# Sheet1.net
KiCad netlist of a schematic drawn in Altium Designer
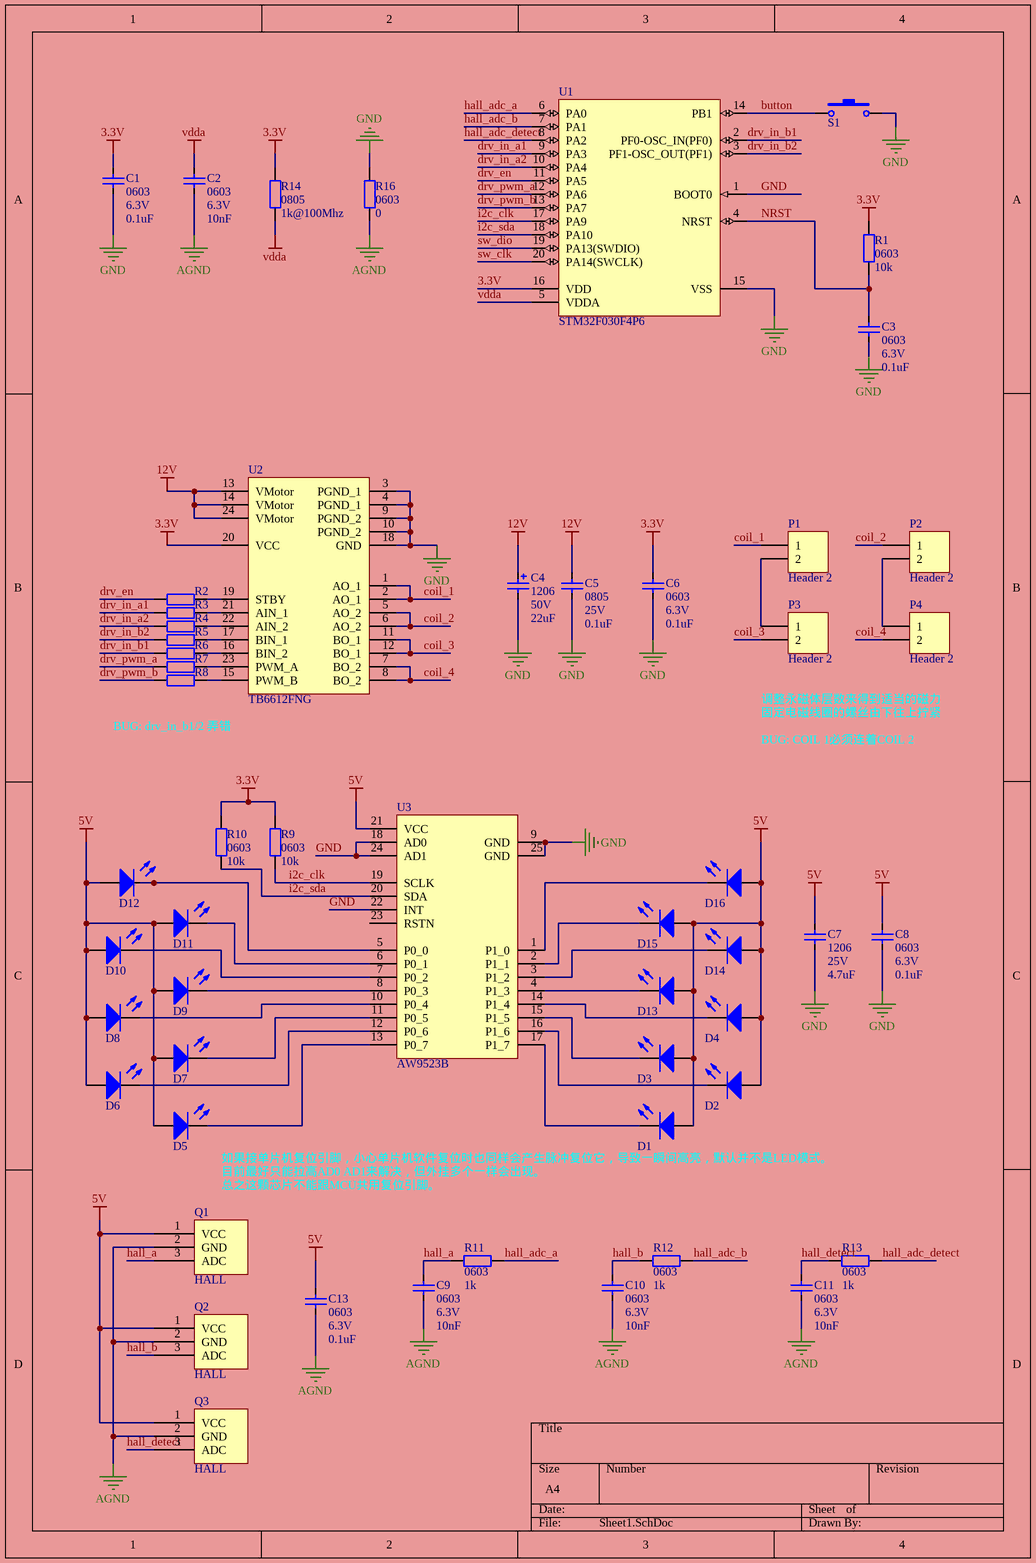
[diagram p0: Sheet1.SchDoc]

(export (version "E")
  (design (tool "Eeschema 10.0.6"))
  (components
    (comp (ref "C1")
      (value "0.1uF")
      (footprint "0603")
      (description "Capacitor 0603")
      (fields (field (name "VOLTAGE") "6.3V") (field (name "Comment") "CAP_0603"))
      (libsource (lib "Charles_Schlib") (part "CAP_0603"))
    )
    (comp (ref "C2")
      (value "10nF")
      (footprint "0603")
      (description "Capacitor 0603")
      (fields (field (name "VOLTAGE") "6.3V") (field (name "Comment") "CAP_0603"))
      (libsource (lib "Charles_Schlib") (part "CAP_0603"))
    )
    (comp (ref "C3")
      (value "0.1uF")
      (footprint "0603")
      (description "Capacitor 0603")
      (fields (field (name "VOLTAGE") "6.3V") (field (name "Comment") "CAP_0603"))
      (libsource (lib "Charles_Schlib") (part "CAP_0603"))
    )
    (comp (ref "C4")
      (value "22uF")
      (footprint "1206")
      (description "aluminium electrolysis")
      (fields (field (name "VOLTAGE") "50V") (field (name "Comment") "CAP_Aluminium"))
      (libsource (lib "Charles_Schlib") (part "CAP_Aluminium"))
    )
    (comp (ref "C5")
      (value "0.1uF")
      (footprint "0805")
      (description "Capacitor 0805")
      (fields (field (name "VOLTAGE") "25V") (field (name "Comment") "CAP_0805"))
      (libsource (lib "Charles_Schlib") (part "CAP_0805"))
    )
    (comp (ref "C6")
      (value "0.1uF")
      (footprint "0603")
      (description "Capacitor 0603")
      (fields (field (name "VOLTAGE") "6.3V") (field (name "Comment") "CAP_0603"))
      (libsource (lib "Charles_Schlib") (part "CAP_0603"))
    )
    (comp (ref "C7")
      (value "4.7uF")
      (footprint "1206")
      (description "Capacitor 1206")
      (fields (field (name "VOLTAGE") "25V") (field (name "Comment") "CAP_1206"))
      (libsource (lib "Charles_Schlib") (part "CAP_1206"))
    )
    (comp (ref "C8")
      (value "0.1uF")
      (footprint "0603")
      (description "Capacitor 0603")
      (fields (field (name "VOLTAGE") "6.3V") (field (name "Comment") "CAP_0603"))
      (libsource (lib "Charles_Schlib") (part "CAP_0603"))
    )
    (comp (ref "C9")
      (value "10nF")
      (footprint "0603")
      (description "Capacitor 0603")
      (fields (field (name "VOLTAGE") "6.3V") (field (name "Comment") "CAP_0603"))
      (libsource (lib "Charles_Schlib") (part "CAP_0603"))
    )
    (comp (ref "C10")
      (value "10nF")
      (footprint "0603")
      (description "Capacitor 0603")
      (fields (field (name "VOLTAGE") "6.3V") (field (name "Comment") "CAP_0603"))
      (libsource (lib "Charles_Schlib") (part "CAP_0603"))
    )
    (comp (ref "C11")
      (value "10nF")
      (footprint "0603")
      (description "Capacitor 0603")
      (fields (field (name "VOLTAGE") "6.3V") (field (name "Comment") "CAP_0603"))
      (libsource (lib "Charles_Schlib") (part "CAP_0603"))
    )
    (comp (ref "C13")
      (value "0.1uF")
      (footprint "0603")
      (description "Capacitor 0603")
      (fields (field (name "VOLTAGE") "6.3V") (field (name "Comment") "CAP_0603"))
      (libsource (lib "Charles_Schlib") (part "CAP_0603"))
    )
    (comp (ref "D1")
      (value "LED")
      (footprint "LED_DIP")
      (description "LED_DIP")
      (libsource (lib "Charles_Schlib") (part "LED_DIP"))
    )
    (comp (ref "D2")
      (value "LED")
      (footprint "LED_DIP")
      (description "LED_DIP")
      (libsource (lib "Charles_Schlib") (part "LED_DIP"))
    )
    (comp (ref "D3")
      (value "LED")
      (footprint "LED_DIP")
      (description "LED_DIP")
      (libsource (lib "Charles_Schlib") (part "LED_DIP"))
    )
    (comp (ref "D4")
      (value "LED")
      (footprint "LED_DIP")
      (description "LED_DIP")
      (libsource (lib "Charles_Schlib") (part "LED_DIP"))
    )
    (comp (ref "D5")
      (value "LED")
      (footprint "LED_DIP")
      (description "LED_DIP")
      (libsource (lib "Charles_Schlib") (part "LED_DIP"))
    )
    (comp (ref "D6")
      (value "LED")
      (footprint "LED_DIP")
      (description "LED_DIP")
      (libsource (lib "Charles_Schlib") (part "LED_DIP"))
    )
    (comp (ref "D7")
      (value "LED")
      (footprint "LED_DIP")
      (description "LED_DIP")
      (libsource (lib "Charles_Schlib") (part "LED_DIP"))
    )
    (comp (ref "D8")
      (value "LED")
      (footprint "LED_DIP")
      (description "LED_DIP")
      (libsource (lib "Charles_Schlib") (part "LED_DIP"))
    )
    (comp (ref "D9")
      (value "LED")
      (footprint "LED_DIP")
      (description "LED_DIP")
      (libsource (lib "Charles_Schlib") (part "LED_DIP"))
    )
    (comp (ref "D10")
      (value "LED")
      (footprint "LED_DIP")
      (description "LED_DIP")
      (libsource (lib "Charles_Schlib") (part "LED_DIP"))
    )
    (comp (ref "D11")
      (value "LED")
      (footprint "LED_DIP")
      (description "LED_DIP")
      (libsource (lib "Charles_Schlib") (part "LED_DIP"))
    )
    (comp (ref "D12")
      (value "LED")
      (footprint "LED_DIP")
      (description "LED_DIP")
      (libsource (lib "Charles_Schlib") (part "LED_DIP"))
    )
    (comp (ref "D13")
      (value "LED")
      (footprint "LED_DIP")
      (description "LED_DIP")
      (libsource (lib "Charles_Schlib") (part "LED_DIP"))
    )
    (comp (ref "D14")
      (value "LED")
      (footprint "LED_DIP")
      (description "LED_DIP")
      (libsource (lib "Charles_Schlib") (part "LED_DIP"))
    )
    (comp (ref "D15")
      (value "LED")
      (footprint "LED_DIP")
      (description "LED_DIP")
      (libsource (lib "Charles_Schlib") (part "LED_DIP"))
    )
    (comp (ref "D16")
      (value "LED")
      (footprint "LED_DIP")
      (description "LED_DIP")
      (libsource (lib "Charles_Schlib") (part "LED_DIP"))
    )
    (comp (ref "P1")
      (value "Header 2")
      (footprint "HDR1X2")
      (description "Header, 2-Pin")
      (fields (field (name "PUBLISHER") "Altium Limited"))
      (libsource (lib "Miscellaneous Connectors") (part "Header 2"))
    )
    (comp (ref "P2")
      (value "Header 2")
      (footprint "HDR1X2")
      (description "Header, 2-Pin")
      (fields (field (name "PUBLISHER") "Altium Limited"))
      (libsource (lib "Miscellaneous Connectors") (part "Header 2"))
    )
    (comp (ref "P3")
      (value "Header 2")
      (footprint "HDR1X2")
      (description "Header, 2-Pin")
      (fields (field (name "PUBLISHER") "Altium Limited"))
      (libsource (lib "Miscellaneous Connectors") (part "Header 2"))
    )
    (comp (ref "P4")
      (value "Header 2")
      (footprint "HDR1X2")
      (description "Header, 2-Pin")
      (fields (field (name "PUBLISHER") "Altium Limited"))
      (libsource (lib "Miscellaneous Connectors") (part "Header 2"))
    )
    (comp (ref "Q1")
      (value "HALL")
      (footprint "HALL_3503_TO-92")
      (description "HALL SS49E 3503")
      (libsource (lib "Charles_Schlib") (part "SS49E_3503"))
    )
    (comp (ref "Q2")
      (value "HALL")
      (footprint "HALL_3503_TO-92")
      (description "HALL SS49E 3503")
      (libsource (lib "Charles_Schlib") (part "SS49E_3503"))
    )
    (comp (ref "Q3")
      (value "HALL")
      (footprint "HALL_3503_TO-92")
      (description "HALL SS49E 3503")
      (libsource (lib "Charles_Schlib") (part "SS49E_3503"))
    )
    (comp (ref "R1")
      (value "10k")
      (footprint "0603")
      (description "Resister")
      (fields (field (name "Comment") "RES_0603"))
      (libsource (lib "") (part "RES_0603_1"))
    )
    (comp (ref "R2")
      (value "RES_0603")
      (footprint "R0603")
      (description "Resister")
      (libsource (lib "Charles_Schlib") (part "RES_0603"))
    )
    (comp (ref "R3")
      (value "RES_0603")
      (footprint "R0603")
      (description "Resister")
      (libsource (lib "Charles_Schlib") (part "RES_0603"))
    )
    (comp (ref "R4")
      (value "RES_0603")
      (footprint "R0603")
      (description "Resister")
      (libsource (lib "Charles_Schlib") (part "RES_0603"))
    )
    (comp (ref "R5")
      (value "RES_0603")
      (footprint "R0603")
      (description "Resister")
      (libsource (lib "Charles_Schlib") (part "RES_0603"))
    )
    (comp (ref "R6")
      (value "RES_0603")
      (footprint "R0603")
      (description "Resister")
      (libsource (lib "Charles_Schlib") (part "RES_0603"))
    )
    (comp (ref "R7")
      (value "RES_0603")
      (footprint "R0603")
      (description "Resister")
      (libsource (lib "Charles_Schlib") (part "RES_0603"))
    )
    (comp (ref "R8")
      (value "RES_0603")
      (footprint "R0603")
      (description "Resister")
      (libsource (lib "Charles_Schlib") (part "RES_0603"))
    )
    (comp (ref "R9")
      (value "10k")
      (footprint "0603")
      (description "Resister")
      (fields (field (name "Comment") "RES_0603"))
      (libsource (lib "") (part "RES_0603_1"))
    )
    (comp (ref "R10")
      (value "10k")
      (footprint "0603")
      (description "Resister")
      (fields (field (name "Comment") "RES_0603"))
      (libsource (lib "") (part "RES_0603_1"))
    )
    (comp (ref "R11")
      (value "1k")
      (footprint "0603")
      (description "Resister")
      (fields (field (name "Comment") "RES_0603"))
      (libsource (lib "") (part "RES_0603_2"))
    )
    (comp (ref "R12")
      (value "1k")
      (footprint "0603")
      (description "Resister")
      (fields (field (name "Comment") "RES_0603"))
      (libsource (lib "") (part "RES_0603_2"))
    )
    (comp (ref "R13")
      (value "1k")
      (footprint "0603")
      (description "Resister")
      (fields (field (name "Comment") "RES_0603"))
      (libsource (lib "") (part "RES_0603_2"))
    )
    (comp (ref "R14")
      (value "1k@100Mhz")
      (footprint "0805")
      (description "Resister")
      (fields (field (name "Comment") "RES_0805"))
      (libsource (lib "Charles_Schlib") (part "RES_0805"))
    )
    (comp (ref "R16")
      (value "0")
      (footprint "0603")
      (description "Resister")
      (fields (field (name "Comment") "RES_0603"))
      (libsource (lib "") (part "RES_0603_1"))
    )
    (comp (ref "S1")
      (value "BUTTON")
      (footprint "BUTTON_6X6")
      (description "BUTTON_1_6mm X 6mm SMT")
      (libsource (lib "Charles_Schlib") (part "BUTTON_6x6"))
    )
    (comp (ref "U1")
      (value "STM32F030F4P6")
      (footprint "STM-TSSOP20_N")
      (libsource (lib "STMicroelectronics STM32 F0") (part "STM32F030F4P6"))
    )
    (comp (ref "U2")
      (value "TB6612FNG")
      (footprint "TB6612FNG")
      (description "MOS driver")
      (fields (field (name "PUBLISHER") "Altium Limited"))
      (libsource (lib "Charles_Schlib") (part "TB6612FNG"))
    )
    (comp (ref "U3")
      (value "AW9523B")
      (footprint "AW9523B")
      (description "led driver")
      (libsource (lib "Charles_Schlib") (part "AW9523B"))
    )
  )
  (nets
    (net (code "1") (name "/NRST") (class "Default")
      (node (ref "C3") (pin "2") (pinfunction "2_2") (pintype "passive"))
      (node (ref "R1") (pin "1") (pinfunction "1_1") (pintype "passive"))
      (node (ref "U1") (pin "4") (pinfunction "NRST_4") (pintype "bidirectional"))
    )
    (net (code "2") (name "/button") (class "Default")
      (node (ref "S1") (pin "1") (pinfunction "1_1") (pintype "passive"))
      (node (ref "U1") (pin "14") (pinfunction "PB1_14") (pintype "bidirectional"))
    )
    (net (code "3") (name "/coil_1") (class "Default")
      (node (ref "P1") (pin "1") (pinfunction "1_1") (pintype "passive"))
      (node (ref "U2") (pin "1") (pinfunction "AO_1_1") (pintype "open_collector"))
      (node (ref "U2") (pin "2") (pinfunction "AO_1_2") (pintype "open_collector"))
    )
    (net (code "4") (name "/coil_2") (class "Default")
      (node (ref "P2") (pin "1") (pinfunction "1_1") (pintype "passive"))
      (node (ref "U2") (pin "5") (pinfunction "AO_2_5") (pintype "open_collector"))
      (node (ref "U2") (pin "6") (pinfunction "AO_2_6") (pintype "open_collector"))
    )
    (net (code "5") (name "/coil_3") (class "Default")
      (node (ref "P3") (pin "2") (pinfunction "2_2") (pintype "passive"))
      (node (ref "U2") (pin "11") (pinfunction "BO_1_11") (pintype "open_collector"))
      (node (ref "U2") (pin "12") (pinfunction "BO_1_12") (pintype "open_collector"))
    )
    (net (code "6") (name "/coil_4") (class "Default")
      (node (ref "P4") (pin "2") (pinfunction "2_2") (pintype "passive"))
      (node (ref "U2") (pin "7") (pinfunction "BO_2_7") (pintype "open_collector"))
      (node (ref "U2") (pin "8") (pinfunction "BO_2_8") (pintype "open_collector"))
    )
    (net (code "7") (name "/drv_en") (class "Default")
      (node (ref "R2") (pin "2") (pinfunction "2_2") (pintype "passive"))
      (node (ref "U1") (pin "11") (pinfunction "PA5_11") (pintype "bidirectional"))
    )
    (net (code "8") (name "/drv_in_a1") (class "Default")
      (node (ref "R3") (pin "2") (pinfunction "2_2") (pintype "passive"))
      (node (ref "U1") (pin "9") (pinfunction "PA3_9") (pintype "bidirectional"))
    )
    (net (code "9") (name "/drv_in_a2") (class "Default")
      (node (ref "R4") (pin "2") (pinfunction "2_2") (pintype "passive"))
      (node (ref "U1") (pin "10") (pinfunction "PA4_10") (pintype "bidirectional"))
    )
    (net (code "10") (name "/drv_in_b1") (class "Default")
      (node (ref "R6") (pin "2") (pinfunction "2_2") (pintype "passive"))
      (node (ref "U1") (pin "2") (pinfunction "PF0-OSC_IN(PF0)_2") (pintype "bidirectional"))
    )
    (net (code "11") (name "/drv_in_b2") (class "Default")
      (node (ref "R5") (pin "2") (pinfunction "2_2") (pintype "passive"))
      (node (ref "U1") (pin "3") (pinfunction "PF1-OSC_OUT(PF1)_3") (pintype "bidirectional"))
    )
    (net (code "12") (name "/drv_pwm_a") (class "Default")
      (node (ref "R7") (pin "2") (pinfunction "2_2") (pintype "passive"))
      (node (ref "U1") (pin "12") (pinfunction "PA6_12") (pintype "bidirectional"))
    )
    (net (code "13") (name "/drv_pwm_b") (class "Default")
      (node (ref "R8") (pin "2") (pinfunction "2_2") (pintype "passive"))
      (node (ref "U1") (pin "13") (pinfunction "PA7_13") (pintype "bidirectional"))
    )
    (net (code "14") (name "/hall_a") (class "Default")
      (node (ref "C9") (pin "1") (pinfunction "1_1") (pintype "passive"))
      (node (ref "Q1") (pin "3") (pinfunction "ADC_3") (pintype "passive"))
      (node (ref "R11") (pin "1") (pinfunction "1_1") (pintype "passive"))
    )
    (net (code "15") (name "/hall_adc_a") (class "Default")
      (node (ref "R11") (pin "2") (pinfunction "2_2") (pintype "passive"))
      (node (ref "U1") (pin "6") (pinfunction "PA0_6") (pintype "bidirectional"))
    )
    (net (code "16") (name "/hall_adc_b") (class "Default")
      (node (ref "R12") (pin "2") (pinfunction "2_2") (pintype "passive"))
      (node (ref "U1") (pin "7") (pinfunction "PA1_7") (pintype "bidirectional"))
    )
    (net (code "17") (name "/hall_adc_detect") (class "Default")
      (node (ref "R13") (pin "2") (pinfunction "2_2") (pintype "passive"))
      (node (ref "U1") (pin "8") (pinfunction "PA2_8") (pintype "bidirectional"))
    )
    (net (code "18") (name "/hall_b") (class "Default")
      (node (ref "C10") (pin "1") (pinfunction "1_1") (pintype "passive"))
      (node (ref "Q2") (pin "3") (pinfunction "ADC_3") (pintype "passive"))
      (node (ref "R12") (pin "1") (pinfunction "1_1") (pintype "passive"))
    )
    (net (code "19") (name "/hall_detect") (class "Default")
      (node (ref "C11") (pin "1") (pinfunction "1_1") (pintype "passive"))
      (node (ref "Q3") (pin "3") (pinfunction "ADC_3") (pintype "passive"))
      (node (ref "R13") (pin "1") (pinfunction "1_1") (pintype "passive"))
    )
    (net (code "20") (name "/i2c_clk") (class "Default")
      (node (ref "R9") (pin "1") (pinfunction "1_1") (pintype "passive"))
      (node (ref "U1") (pin "17") (pinfunction "PA9_17") (pintype "bidirectional"))
      (node (ref "U3") (pin "19") (pinfunction "SCLK_19") (pintype "passive"))
    )
    (net (code "21") (name "/i2c_sda") (class "Default")
      (node (ref "R10") (pin "1") (pinfunction "1_1") (pintype "passive"))
      (node (ref "U1") (pin "18") (pinfunction "PA10_18") (pintype "bidirectional"))
      (node (ref "U3") (pin "20") (pinfunction "SDA_20") (pintype "passive"))
    )
    (net (code "22") (name "/sw_clk") (class "Default")
      (node (ref "U1") (pin "20") (pinfunction "PA14(SWCLK)_20") (pintype "bidirectional"))
    )
    (net (code "23") (name "/sw_dio") (class "Default")
      (node (ref "U1") (pin "19") (pinfunction "PA13(SWDIO)_19") (pintype "bidirectional"))
    )
    (net (code "24") (name "3.3V") (class "Default")
      (node (ref "C1") (pin "2") (pinfunction "2_2") (pintype "passive"))
      (node (ref "C6") (pin "2") (pinfunction "2_2") (pintype "passive"))
      (node (ref "R1") (pin "2") (pinfunction "2_2") (pintype "passive"))
      (node (ref "R10") (pin "2") (pinfunction "2_2") (pintype "passive"))
      (node (ref "R14") (pin "2") (pinfunction "2_2") (pintype "passive"))
      (node (ref "R9") (pin "2") (pinfunction "2_2") (pintype "passive"))
      (node (ref "U1") (pin "16") (pinfunction "VDD_16") (pintype "power_in"))
      (node (ref "U2") (pin "20") (pinfunction "VCC_20") (pintype "power_in"))
    )
    (net (code "25") (name "5V") (class "Default")
      (node (ref "C13") (pin "2") (pinfunction "2_2") (pintype "passive"))
      (node (ref "C7") (pin "2") (pinfunction "2_2") (pintype "passive"))
      (node (ref "C8") (pin "2") (pinfunction "2_2") (pintype "passive"))
      (node (ref "D1") (pin "1") (pintype "passive"))
      (node (ref "D10") (pin "1") (pintype "passive"))
      (node (ref "D11") (pin "1") (pintype "passive"))
      (node (ref "D12") (pin "1") (pintype "passive"))
      (node (ref "D13") (pin "1") (pintype "passive"))
      (node (ref "D14") (pin "1") (pintype "passive"))
      (node (ref "D15") (pin "1") (pintype "passive"))
      (node (ref "D16") (pin "1") (pintype "passive"))
      (node (ref "D2") (pin "1") (pintype "passive"))
      (node (ref "D3") (pin "1") (pintype "passive"))
      (node (ref "D4") (pin "1") (pintype "passive"))
      (node (ref "D5") (pin "1") (pintype "passive"))
      (node (ref "D6") (pin "1") (pintype "passive"))
      (node (ref "D7") (pin "1") (pintype "passive"))
      (node (ref "D8") (pin "1") (pintype "passive"))
      (node (ref "D9") (pin "1") (pintype "passive"))
      (node (ref "Q1") (pin "1") (pinfunction "VCC_1") (pintype "passive"))
      (node (ref "Q2") (pin "1") (pinfunction "VCC_1") (pintype "passive"))
      (node (ref "Q3") (pin "1") (pinfunction "VCC_1") (pintype "passive"))
      (node (ref "U3") (pin "21") (pinfunction "VCC_21") (pintype "passive"))
    )
    (net (code "26") (name "12V") (class "Default")
      (node (ref "C4") (pin "1") (pinfunction "1_1") (pintype "passive"))
      (node (ref "C5") (pin "2") (pinfunction "2_2") (pintype "passive"))
      (node (ref "U2") (pin "13") (pinfunction "VMotor_13") (pintype "power_in"))
      (node (ref "U2") (pin "14") (pinfunction "VMotor_14") (pintype "power_in"))
      (node (ref "U2") (pin "24") (pinfunction "VMotor_24") (pintype "power_in"))
    )
    (net (code "27") (name "AGND") (class "Default")
      (node (ref "C10") (pin "2") (pinfunction "2_2") (pintype "passive"))
      (node (ref "C11") (pin "2") (pinfunction "2_2") (pintype "passive"))
      (node (ref "C13") (pin "1") (pinfunction "1_1") (pintype "passive"))
      (node (ref "C2") (pin "1") (pinfunction "1_1") (pintype "passive"))
      (node (ref "C9") (pin "2") (pinfunction "2_2") (pintype "passive"))
      (node (ref "Q1") (pin "2") (pinfunction "GND_2") (pintype "passive"))
      (node (ref "Q2") (pin "2") (pinfunction "GND_2") (pintype "passive"))
      (node (ref "Q3") (pin "2") (pinfunction "GND_2") (pintype "passive"))
      (node (ref "R16") (pin "1") (pinfunction "1_1") (pintype "passive"))
    )
    (net (code "28") (name "GND") (class "Default")
      (node (ref "C1") (pin "1") (pinfunction "1_1") (pintype "passive"))
      (node (ref "C3") (pin "1") (pinfunction "1_1") (pintype "passive"))
      (node (ref "C4") (pin "2") (pinfunction "2_2") (pintype "passive"))
      (node (ref "C5") (pin "1") (pinfunction "1_1") (pintype "passive"))
      (node (ref "C6") (pin "1") (pinfunction "1_1") (pintype "passive"))
      (node (ref "C7") (pin "1") (pinfunction "1_1") (pintype "passive"))
      (node (ref "C8") (pin "1") (pinfunction "1_1") (pintype "passive"))
      (node (ref "R16") (pin "2") (pinfunction "2_2") (pintype "passive"))
      (node (ref "S1") (pin "2") (pinfunction "2_2") (pintype "passive"))
      (node (ref "U1") (pin "1") (pinfunction "BOOT0_1") (pintype "input"))
      (node (ref "U1") (pin "15") (pinfunction "VSS_15") (pintype "power_in"))
      (node (ref "U2") (pin "10") (pinfunction "PGND_2_10") (pintype "power_in"))
      (node (ref "U2") (pin "18") (pinfunction "GND_18") (pintype "power_in"))
      (node (ref "U2") (pin "3") (pinfunction "PGND_1_3") (pintype "power_in"))
      (node (ref "U2") (pin "4") (pinfunction "PGND_1_4") (pintype "power_in"))
      (node (ref "U2") (pin "9") (pinfunction "PGND_2_9") (pintype "power_in"))
      (node (ref "U3") (pin "18") (pinfunction "AD0_18") (pintype "passive"))
      (node (ref "U3") (pin "22") (pinfunction "INT_22") (pintype "passive"))
      (node (ref "U3") (pin "24") (pinfunction "AD1_24") (pintype "passive"))
      (node (ref "U3") (pin "25") (pinfunction "GND_25") (pintype "passive"))
      (node (ref "U3") (pin "9") (pinfunction "GND_9") (pintype "passive"))
    )
    (net (code "29") (name "Net-(P1-Pad2)") (class "Default")
      (node (ref "P1") (pin "2") (pinfunction "2_2") (pintype "passive"))
      (node (ref "P3") (pin "1") (pinfunction "1_1") (pintype "passive"))
    )
    (net (code "30") (name "Net-(P2-Pad2)") (class "Default")
      (node (ref "P2") (pin "2") (pinfunction "2_2") (pintype "passive"))
      (node (ref "P4") (pin "1") (pinfunction "1_1") (pintype "passive"))
    )
    (net (code "31") (name "Net-(U2-AIN_1)") (class "Default")
      (node (ref "R3") (pin "1") (pinfunction "1_1") (pintype "passive"))
      (node (ref "U2") (pin "21") (pinfunction "AIN_1_21") (pintype "open_collector"))
    )
    (net (code "32") (name "Net-(U2-AIN_2)") (class "Default")
      (node (ref "R4") (pin "1") (pinfunction "1_1") (pintype "passive"))
      (node (ref "U2") (pin "22") (pinfunction "AIN_2_22") (pintype "open_collector"))
    )
    (net (code "33") (name "Net-(U2-BIN_1)") (class "Default")
      (node (ref "R5") (pin "1") (pinfunction "1_1") (pintype "passive"))
      (node (ref "U2") (pin "17") (pinfunction "BIN_1_17") (pintype "open_collector"))
    )
    (net (code "34") (name "Net-(U2-BIN_2)") (class "Default")
      (node (ref "R6") (pin "1") (pinfunction "1_1") (pintype "passive"))
      (node (ref "U2") (pin "16") (pinfunction "BIN_2_16") (pintype "open_collector"))
    )
    (net (code "35") (name "Net-(U2-PWM_A)") (class "Default")
      (node (ref "R7") (pin "1") (pinfunction "1_1") (pintype "passive"))
      (node (ref "U2") (pin "23") (pinfunction "PWM_A_23") (pintype "open_collector"))
    )
    (net (code "36") (name "Net-(U2-PWM_B)") (class "Default")
      (node (ref "R8") (pin "1") (pinfunction "1_1") (pintype "passive"))
      (node (ref "U2") (pin "15") (pinfunction "PWM_B_15") (pintype "open_collector"))
    )
    (net (code "37") (name "Net-(U2-STBY)") (class "Default")
      (node (ref "R2") (pin "1") (pinfunction "1_1") (pintype "passive"))
      (node (ref "U2") (pin "19") (pinfunction "STBY_19") (pintype "open_collector"))
    )
    (net (code "38") (name "Net-(U3-P0_0)") (class "Default")
      (node (ref "D12") (pin "2") (pintype "passive"))
      (node (ref "U3") (pin "5") (pinfunction "P0_0_5") (pintype "passive"))
    )
    (net (code "39") (name "Net-(U3-P0_1)") (class "Default")
      (node (ref "D11") (pin "2") (pintype "passive"))
      (node (ref "U3") (pin "6") (pinfunction "P0_1_6") (pintype "passive"))
    )
    (net (code "40") (name "Net-(U3-P0_2)") (class "Default")
      (node (ref "D10") (pin "2") (pintype "passive"))
      (node (ref "U3") (pin "7") (pinfunction "P0_2_7") (pintype "passive"))
    )
    (net (code "41") (name "Net-(U3-P0_3)") (class "Default")
      (node (ref "D9") (pin "2") (pintype "passive"))
      (node (ref "U3") (pin "8") (pinfunction "P0_3_8") (pintype "passive"))
    )
    (net (code "42") (name "Net-(U3-P0_4)") (class "Default")
      (node (ref "D8") (pin "2") (pintype "passive"))
      (node (ref "U3") (pin "10") (pinfunction "P0_4_10") (pintype "passive"))
    )
    (net (code "43") (name "Net-(U3-P0_5)") (class "Default")
      (node (ref "D7") (pin "2") (pintype "passive"))
      (node (ref "U3") (pin "11") (pinfunction "P0_5_11") (pintype "passive"))
    )
    (net (code "44") (name "Net-(U3-P0_6)") (class "Default")
      (node (ref "D6") (pin "2") (pintype "passive"))
      (node (ref "U3") (pin "12") (pinfunction "P0_6_12") (pintype "passive"))
    )
    (net (code "45") (name "Net-(U3-P0_7)") (class "Default")
      (node (ref "D5") (pin "2") (pintype "passive"))
      (node (ref "U3") (pin "13") (pinfunction "P0_7_13") (pintype "passive"))
    )
    (net (code "46") (name "Net-(U3-P1_0)") (class "Default")
      (node (ref "D16") (pin "2") (pintype "passive"))
      (node (ref "U3") (pin "1") (pinfunction "P1_0_1") (pintype "passive"))
    )
    (net (code "47") (name "Net-(U3-P1_1)") (class "Default")
      (node (ref "D15") (pin "2") (pintype "passive"))
      (node (ref "U3") (pin "2") (pinfunction "P1_1_2") (pintype "passive"))
    )
    (net (code "48") (name "Net-(U3-P1_2)") (class "Default")
      (node (ref "D14") (pin "2") (pintype "passive"))
      (node (ref "U3") (pin "3") (pinfunction "P1_2_3") (pintype "passive"))
    )
    (net (code "49") (name "Net-(U3-P1_3)") (class "Default")
      (node (ref "D13") (pin "2") (pintype "passive"))
      (node (ref "U3") (pin "4") (pinfunction "P1_3_4") (pintype "passive"))
    )
    (net (code "50") (name "Net-(U3-P1_4)") (class "Default")
      (node (ref "D4") (pin "2") (pintype "passive"))
      (node (ref "U3") (pin "14") (pinfunction "P1_4_14") (pintype "passive"))
    )
    (net (code "51") (name "Net-(U3-P1_5)") (class "Default")
      (node (ref "D3") (pin "2") (pintype "passive"))
      (node (ref "U3") (pin "15") (pinfunction "P1_5_15") (pintype "passive"))
    )
    (net (code "52") (name "Net-(U3-P1_6)") (class "Default")
      (node (ref "D2") (pin "2") (pintype "passive"))
      (node (ref "U3") (pin "16") (pinfunction "P1_6_16") (pintype "passive"))
    )
    (net (code "53") (name "Net-(U3-P1_7)") (class "Default")
      (node (ref "D1") (pin "2") (pintype "passive"))
      (node (ref "U3") (pin "17") (pinfunction "P1_7_17") (pintype "passive"))
    )
    (net (code "54") (name "unconnected-(U3-RSTN-Pad23)") (class "Default")
      (node (ref "U3") (pin "23") (pinfunction "RSTN_23") (pintype "passive"))
    )
    (net (code "55") (name "vdda") (class "Default")
      (node (ref "C2") (pin "2") (pinfunction "2_2") (pintype "passive"))
      (node (ref "R14") (pin "1") (pinfunction "1_1") (pintype "passive"))
      (node (ref "U1") (pin "5") (pinfunction "VDDA_5") (pintype "power_in"))
    )
  )
)
